# JWpulsegen-V2.net
KiCad netlist of a schematic drawn in Altium Designer
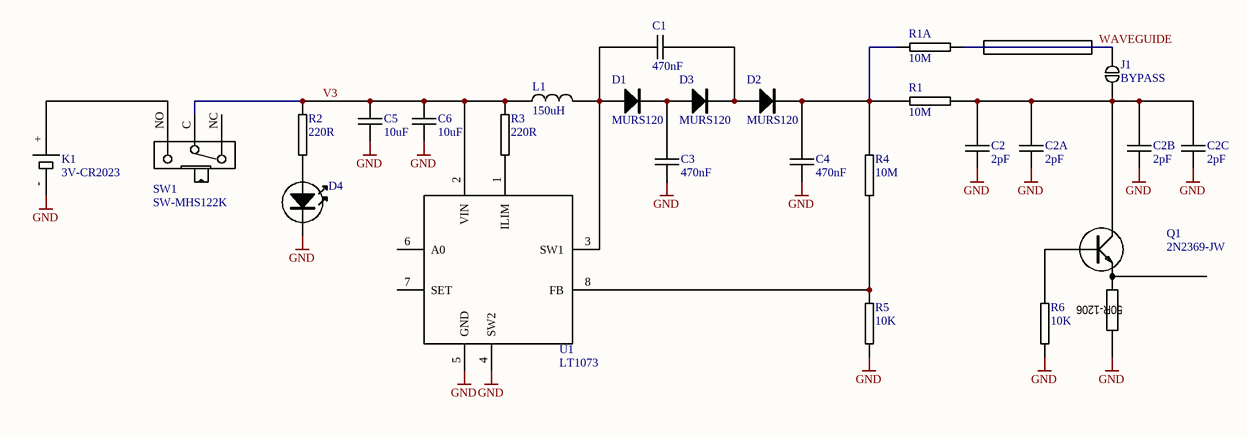
[diagram p0: JWpulsegen-V2.SchDoc]

(export (version "E")
  (design (tool "Eeschema 10.0.6"))
  (components
    (comp (ref "C1")
      (value "470nF")
      (footprint "1812C-GENERIC")
      (description "CAPACITOR 1812 CERAMIC")
      (libsource (lib "SMD Capacitors Other") (part "1812C-470nF-250V-X7R-MUR"))
    )
    (comp (ref "C2")
      (value "2pF")
      (footprint "0805C-GENERIC")
      (description "CAPACITOR 0805 CERAMIC")
      (fields (field (name "TOLERANCE") "±20%") (field (name "MANUFACTURER") "Panasonic - ECG"))
      (libsource (lib "vh_Altium Library") (part "0805C-10UF-6V3-X5R-PAN"))
    )
    (comp (ref "C2A")
      (value "2pF")
      (footprint "0805C-GENERIC")
      (description "CAPACITOR 0805 CERAMIC")
      (fields (field (name "TOLERANCE") "±20%") (field (name "MANUFACTURER") "Panasonic - ECG"))
      (libsource (lib "vh_Altium Library") (part "0805C-10UF-6V3-X5R-PAN"))
    )
    (comp (ref "C2B")
      (value "2pF")
      (footprint "0805C-GENERIC")
      (description "CAPACITOR 0805 CERAMIC")
      (fields (field (name "TOLERANCE") "±20%") (field (name "MANUFACTURER") "Panasonic - ECG"))
      (libsource (lib "vh_Altium Library") (part "0805C-10UF-6V3-X5R-PAN"))
    )
    (comp (ref "C2C")
      (value "2pF")
      (footprint "0805C-GENERIC")
      (description "CAPACITOR 0805 CERAMIC")
      (fields (field (name "TOLERANCE") "±20%") (field (name "MANUFACTURER") "Panasonic - ECG"))
      (libsource (lib "vh_Altium Library") (part "0805C-10UF-6V3-X5R-PAN"))
    )
    (comp (ref "C3")
      (value "470nF")
      (footprint "1812C-GENERIC")
      (description "CAPACITOR 1812 CERAMIC")
      (libsource (lib "SMD Capacitors Other") (part "1812C-470nF-250V-X7R-MUR"))
    )
    (comp (ref "C4")
      (value "470nF")
      (footprint "1812C-GENERIC")
      (description "CAPACITOR 1812 CERAMIC")
      (libsource (lib "SMD Capacitors Other") (part "1812C-470nF-250V-X7R-MUR"))
    )
    (comp (ref "C5")
      (value "10uF")
      (footprint "0805C-GENERIC")
      (description "CAPACITOR 0805 CERAMIC")
      (fields (field (name "TOLERANCE") "±20%") (field (name "MANUFACTURER") "Panasonic - ECG"))
      (libsource (lib "vh_Altium Library") (part "0805C-10UF-6V3-X5R-PAN"))
    )
    (comp (ref "C6")
      (value "10uF")
      (footprint "0805C-GENERIC")
      (description "CAPACITOR 0805 CERAMIC")
      (fields (field (name "TOLERANCE") "±20%") (field (name "MANUFACTURER") "Panasonic - ECG"))
      (libsource (lib "vh_Altium Library") (part "0805C-10UF-6V3-X5R-PAN"))
    )
    (comp (ref "D1")
      (value "MURS120")
      (footprint "DIODE-SMB")
      (description "DIODE")
      (libsource (lib "SMD Diodes") (part "MURS120"))
    )
    (comp (ref "D2")
      (value "MURS120")
      (footprint "DIODE-SMB")
      (description "DIODE")
      (libsource (lib "SMD Diodes") (part "MURS120"))
    )
    (comp (ref "D3")
      (value "MURS120")
      (footprint "DIODE-SMB")
      (description "DIODE")
      (libsource (lib "SMD Diodes") (part "MURS120"))
    )
    (comp (ref "D4")
      (value "LED-YELLOW-3MM")
      (footprint "LED-3MM-YELLOW")
      (libsource (lib "vh_Altium Library") (part "LED-YELLOW-3MM"))
    )
    (comp (ref "J1")
      (value "BYPASS")
      (footprint "BYPASS")
      (description "SOLDERDOT BYPASS")
      (libsource (lib "vh_Altium Library") (part "BYPASS"))
    )
    (comp (ref "K1")
      (value "3V-CR2023")
      (footprint "BATCLIP-CR2032")
      (description "BU2032SM-HD-G")
      (libsource (lib "SMD Connectors") (part "BATCLIP-CR2032-SMD"))
    )
    (comp (ref "L1")
      (value "150uH")
      (footprint "TOKO-NR4018")
      (libsource (lib "SMD Magnetics") (part "150U-NR4018-TOKO"))
    )
    (comp (ref "Q1")
      (value "2N2369-JW")
      (footprint "JW2N2369")
      (libsource (lib "Specials") (part "2N2369-JW"))
    )
    (comp (ref "R1")
      (value "10M")
      (footprint "0805R-TBD")
      (description "RESISTOR 0805 VALUE TO BE DETERMINED")
      (libsource (lib "vh_Altium Library") (part "0805R-10M"))
    )
    (comp (ref "R1A")
      (value "10M")
      (footprint "0805R-TBD")
      (description "RESISTOR 0805 VALUE TO BE DETERMINED")
      (libsource (lib "vh_Altium Library") (part "0805R-10M"))
    )
    (comp (ref "R2")
      (value "220R")
      (footprint "0805R-220")
      (description "RESISTOR 0805 1/4 WATT THIN FILM")
      (libsource (lib "vh_Altium Library") (part "0805R-220"))
    )
    (comp (ref "R3")
      (value "220R")
      (footprint "0805R-220")
      (description "RESISTOR 0805 1/4 WATT THIN FILM")
      (libsource (lib "vh_Altium Library") (part "0805R-220"))
    )
    (comp (ref "R4")
      (value "10M")
      (footprint "0805R-TBD")
      (description "RESISTOR 0805 VALUE TO BE DETERMINED")
      (libsource (lib "vh_Altium Library") (part "0805R-10M"))
    )
    (comp (ref "R5")
      (value "10K")
      (footprint "0805R-10K")
      (description "RESISTOR 0805 1/4 WATT THIN FILM")
      (libsource (lib "vh_Altium Library") (part "0805R-10K"))
    )
    (comp (ref "R6")
      (value "10K")
      (footprint "0805R-10K")
      (description "RESISTOR 0805 1/4 WATT THIN FILM")
      (libsource (lib "vh_Altium Library") (part "0805R-10K"))
    )
    (comp (ref "SW1")
      (value "SW-MHS122K")
      (footprint "MHS122K")
      (description "SWITCH DPDT")
      (libsource (lib "Schlib1") (part "SW-MHS122K"))
    )
    (comp (ref "U1") (value "LT1073") (footprint "SO8") (libsource (lib "IC Regulators") (part "LT1073")))
  )
  (nets
    (net (code "1") (name "/V3") (class "Default")
      (node (ref "C5") (pin "1") (pintype "passive"))
      (node (ref "C6") (pin "1") (pintype "passive"))
      (node (ref "L1") (pin "1") (pinfunction "1_1") (pintype "passive"))
      (node (ref "R2") (pin "1") (pintype "passive"))
      (node (ref "R3") (pin "1") (pintype "passive"))
      (node (ref "SW1") (pin "C") (pintype "passive"))
      (node (ref "U1") (pin "2") (pinfunction "VIN_2") (pintype "passive"))
    )
    (net (code "2") (name "/WAVEGUIDE") (class "Default")
      (node (ref "J1") (pin "1") (pinfunction "1_1") (pintype "passive"))
      (node (ref "R1A") (pin "2") (pintype "passive"))
    )
    (net (code "3") (name "GND") (class "Default")
      (node (ref "C2") (pin "2") (pintype "passive"))
      (node (ref "C2A") (pin "2") (pintype "passive"))
      (node (ref "C2B") (pin "2") (pintype "passive"))
      (node (ref "C2C") (pin "2") (pintype "passive"))
      (node (ref "C3") (pin "1") (pintype "passive"))
      (node (ref "C4") (pin "1") (pintype "passive"))
      (node (ref "C5") (pin "2") (pintype "passive"))
      (node (ref "C6") (pin "2") (pintype "passive"))
      (node (ref "D4") (pin "K") (pintype "passive"))
      (node (ref "K1") (pin "-") (pintype "passive"))
      (node (ref "Q1") (pin "G") (pintype "passive"))
      (node (ref "R5") (pin "2") (pintype "passive"))
      (node (ref "R6") (pin "2") (pintype "passive"))
      (node (ref "U1") (pin "4") (pinfunction "SW2_4") (pintype "passive"))
      (node (ref "U1") (pin "5") (pinfunction "GND_5") (pintype "passive"))
    )
    (net (code "4") (name "Net-(C1-Pad2)") (class "Default")
      (node (ref "C1") (pin "2") (pintype "passive"))
      (node (ref "D2") (pin "A") (pinfunction "A_A") (pintype "passive"))
      (node (ref "D3") (pin "K") (pinfunction "K_K") (pintype "passive"))
    )
    (net (code "5") (name "Net-(C2-Pad1)") (class "Default")
      (node (ref "C2") (pin "1") (pintype "passive"))
      (node (ref "C2A") (pin "1") (pintype "passive"))
      (node (ref "C2B") (pin "1") (pintype "passive"))
      (node (ref "C2C") (pin "1") (pintype "passive"))
      (node (ref "J1") (pin "2") (pinfunction "2_2") (pintype "passive"))
      (node (ref "Q1") (pin "C") (pintype "passive"))
      (node (ref "R1") (pin "2") (pintype "passive"))
    )
    (net (code "6") (name "Net-(C3-Pad2)") (class "Default")
      (node (ref "C3") (pin "2") (pintype "passive"))
      (node (ref "D1") (pin "K") (pinfunction "K_K") (pintype "passive"))
      (node (ref "D3") (pin "A") (pinfunction "A_A") (pintype "passive"))
    )
    (net (code "7") (name "Net-(C4-Pad2)") (class "Default")
      (node (ref "C4") (pin "2") (pintype "passive"))
      (node (ref "D2") (pin "K") (pinfunction "K_K") (pintype "passive"))
      (node (ref "R1") (pin "1") (pintype "passive"))
      (node (ref "R1A") (pin "1") (pintype "passive"))
      (node (ref "R4") (pin "1") (pintype "passive"))
    )
    (net (code "8") (name "Net-(D4-PadA)") (class "Default")
      (node (ref "D4") (pin "A") (pintype "passive"))
      (node (ref "R2") (pin "2") (pintype "passive"))
    )
    (net (code "9") (name "Net-(K1-Pad+)") (class "Default")
      (node (ref "K1") (pin "+") (pintype "passive"))
      (node (ref "SW1") (pin "NO") (pintype "passive"))
    )
    (net (code "10") (name "Net-(Q1-PadB)") (class "Default")
      (node (ref "Q1") (pin "B") (pintype "passive"))
      (node (ref "R6") (pin "1") (pintype "passive"))
    )
    (net (code "11") (name "Net-(U1-FB)") (class "Default")
      (node (ref "R4") (pin "2") (pintype "passive"))
      (node (ref "R5") (pin "1") (pintype "passive"))
      (node (ref "U1") (pin "8") (pinfunction "FB_8") (pintype "passive"))
    )
    (net (code "12") (name "Net-(U1-ILIM)") (class "Default")
      (node (ref "R3") (pin "2") (pintype "passive"))
      (node (ref "U1") (pin "1") (pinfunction "ILIM_1") (pintype "passive"))
    )
    (net (code "13") (name "Net-(U1-SW1)") (class "Default")
      (node (ref "C1") (pin "1") (pintype "passive"))
      (node (ref "D1") (pin "A") (pinfunction "A_A") (pintype "passive"))
      (node (ref "L1") (pin "2") (pinfunction "2_2") (pintype "passive"))
      (node (ref "U1") (pin "3") (pinfunction "SW1_3") (pintype "passive"))
    )
    (net (code "14") (name "unconnected-(SW1-NC2-PadNC)") (class "Default")
      (node (ref "SW1") (pin "NC") (pinfunction "NC2_NC") (pintype "passive"))
    )
    (net (code "15") (name "unconnected-(U1-A0-Pad6)") (class "Default")
      (node (ref "U1") (pin "6") (pinfunction "A0_6") (pintype "passive"))
    )
    (net (code "16") (name "unconnected-(U1-SET-Pad7)") (class "Default")
      (node (ref "U1") (pin "7") (pinfunction "SET_7") (pintype "passive"))
    )
  )
)
